# 05-WPT.net
KiCad netlist of a schematic drawn in Altium Designer
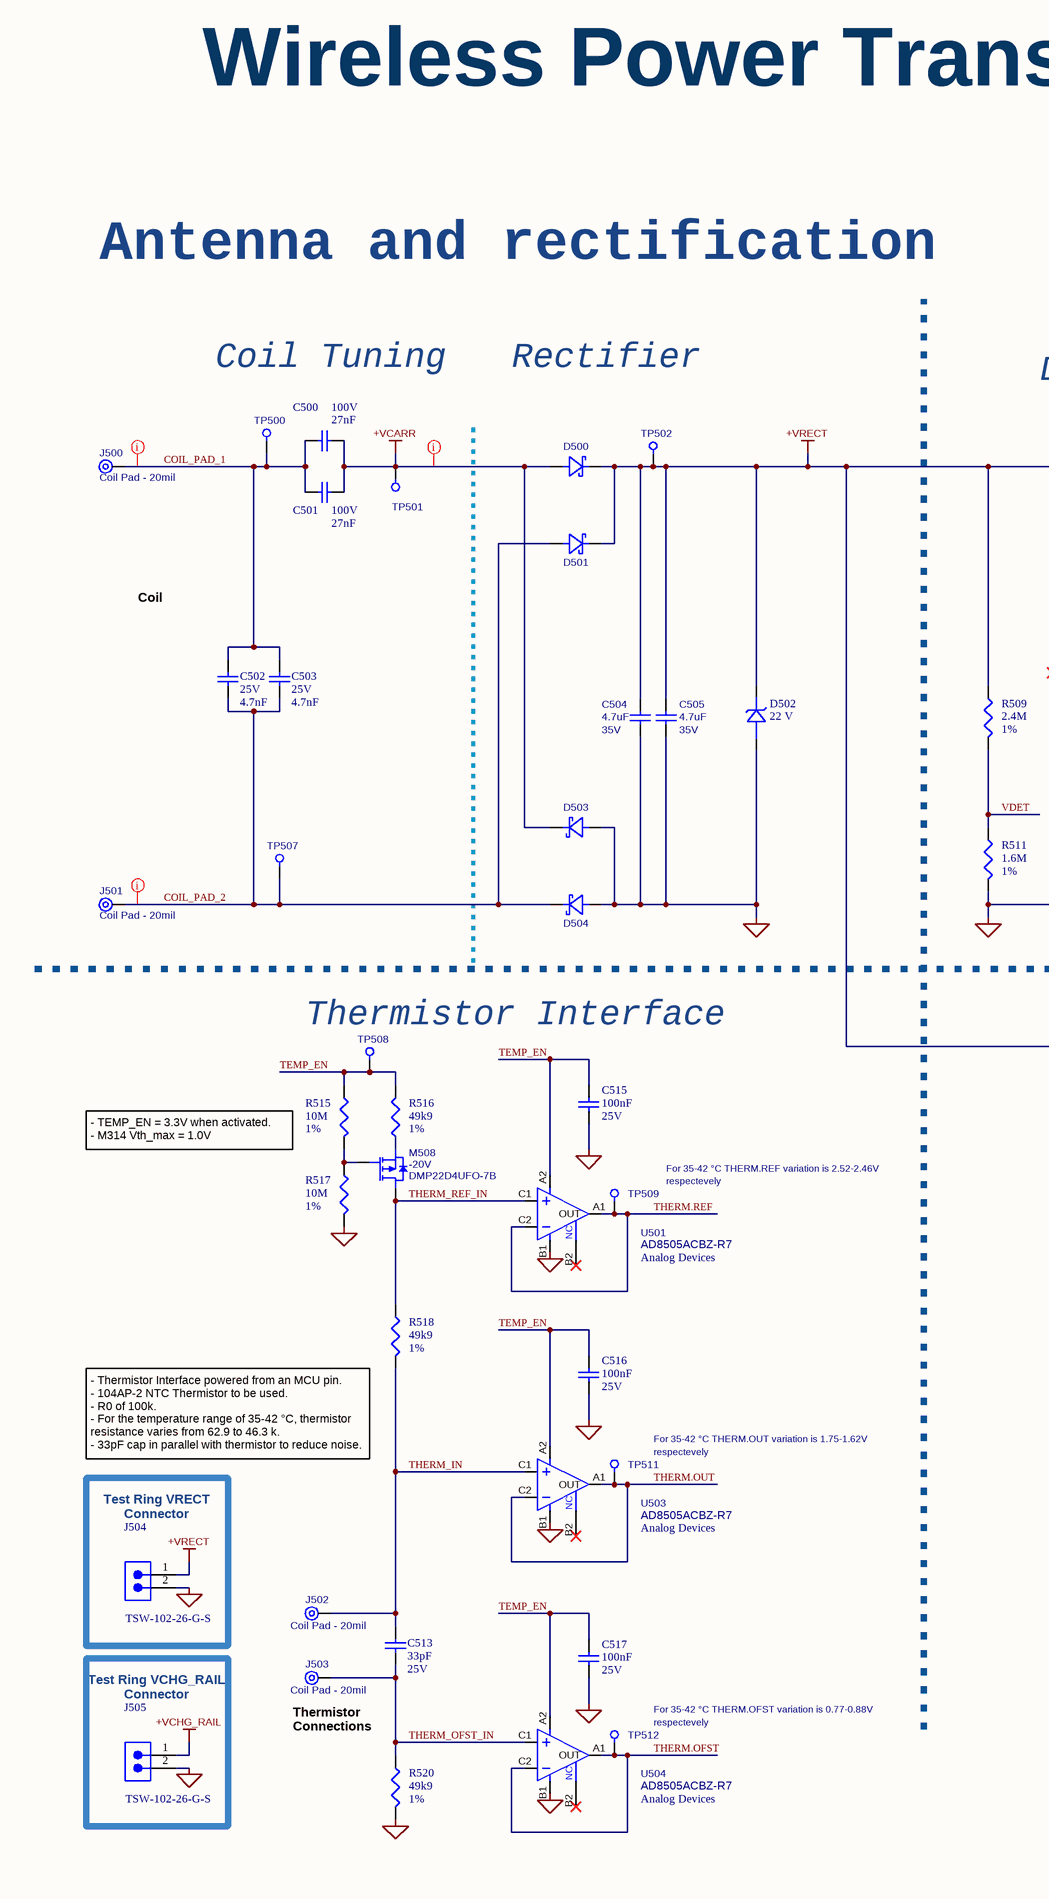
[diagram p0: 05-WPT.SchDoc, left]
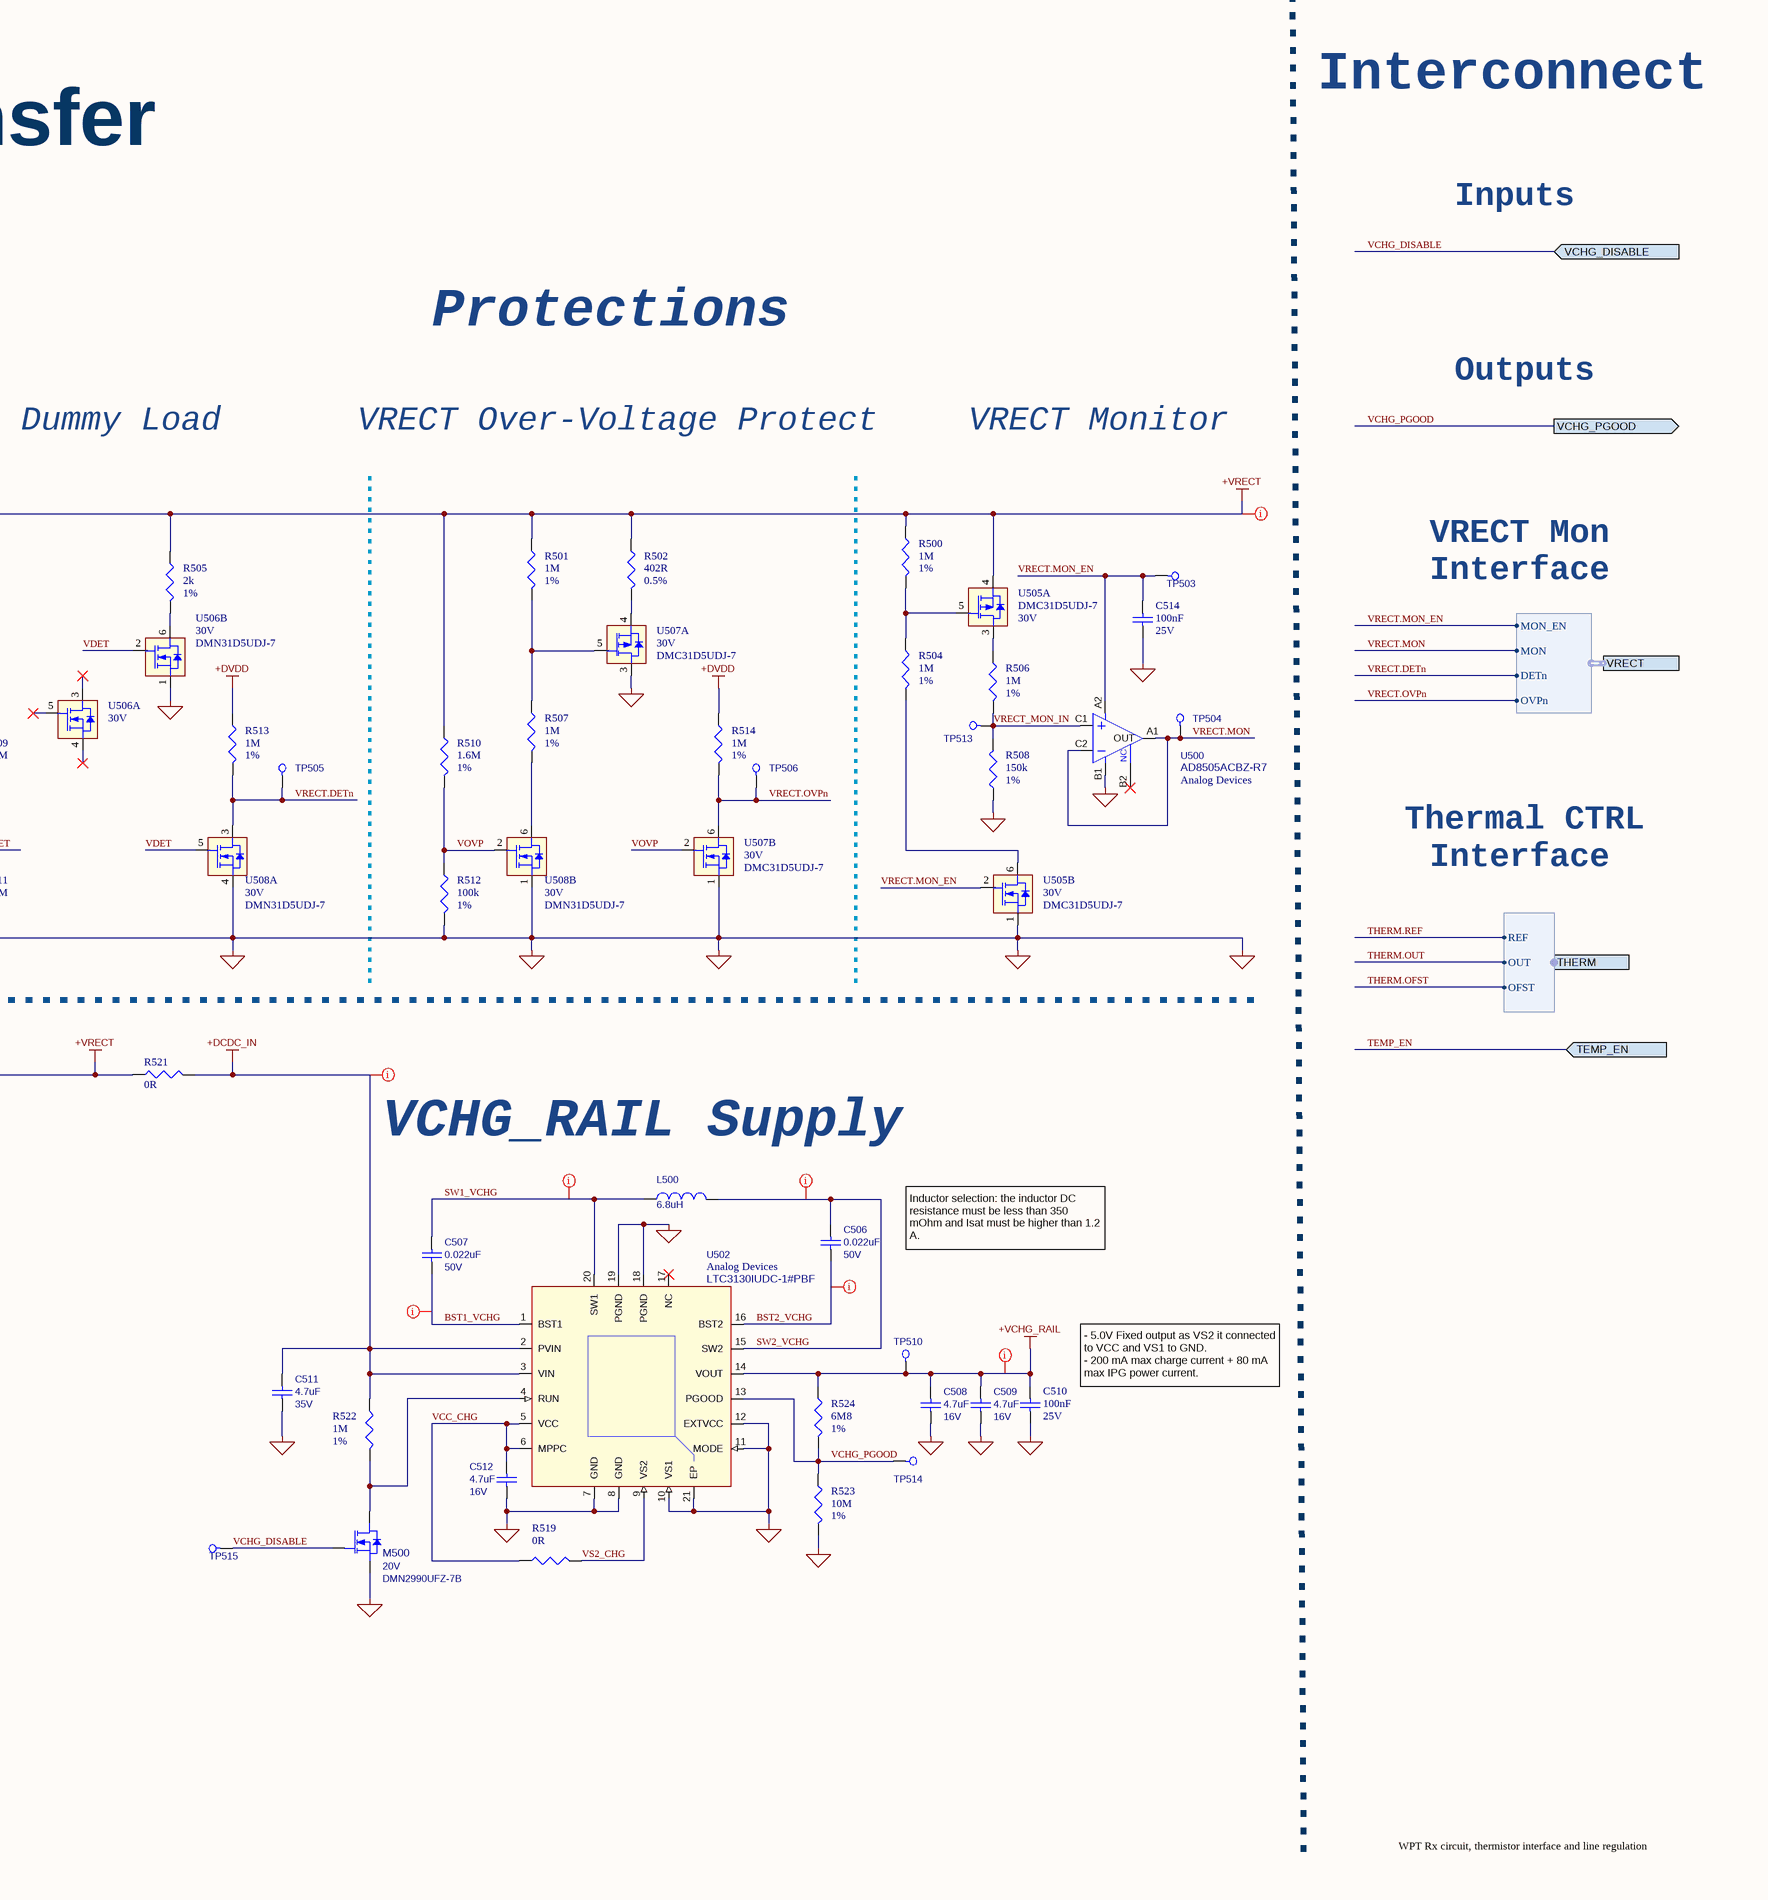
[diagram p1: 05-WPT.SchDoc, right]

(export (version "E")
  (design (tool "Eeschema 10.0.6"))
  (components
    (comp (ref "C500")
      (value "27nF")
      (footprint "CAP0805_REDUCED")
      (description "Capacitor, 27nF, C0G, 100VDC, 2%, 0805, Implant-grade")
      (fields
        (field (name "MANUFACTURER") "Murata")
        (field (name "MANUFACTURER PART NUMBER") "GRM2195C2A273GE01D")
        (field (name "VOLTAGE RATING") "100V")
      )
      (libsource (lib "MP-LIBRARY") (part "GRM2195C2A273GE01D"))
    )
    (comp (ref "C501")
      (value "27nF")
      (footprint "CAP0805_REDUCED")
      (description "Capacitor, 27nF, C0G, 100VDC, 2%, 0805, Implant-grade")
      (fields
        (field (name "MANUFACTURER") "Murata")
        (field (name "MANUFACTURER PART NUMBER") "GRM2195C2A273GE01D")
        (field (name "VOLTAGE RATING") "100V")
      )
      (libsource (lib "MP-LIBRARY") (part "GRM2195C2A273GE01D"))
    )
    (comp (ref "C502")
      (value "4.7nF")
      (footprint "CAP0603_REDUCED")
      (description "Capacitor, 4.7nF, C0G, 25V, 1%, 0603, Implant-grade")
      (fields
        (field (name "MANUFACTURER") "KEMET")
        (field (name "MANUFACTURER PART NUMBER") "C0603C472F3GECTU")
        (field (name "VOLTAGE RATING") "25V")
      )
      (libsource (lib "MP-LIBRARY") (part "C0603C472F3GECTU"))
    )
    (comp (ref "C503")
      (value "4.7nF")
      (footprint "CAP0603_REDUCED")
      (description "Capacitor, 4.7nF, C0G, 25V, 1%, 0603, Implant-grade")
      (fields
        (field (name "MANUFACTURER") "KEMET")
        (field (name "MANUFACTURER PART NUMBER") "C0603C472F3GECTU")
        (field (name "VOLTAGE RATING") "25V")
      )
      (libsource (lib "MP-LIBRARY") (part "C0603C472F3GECTU"))
    )
    (comp (ref "C504")
      (value "4.7uF")
      (footprint "CAP0805_REDUCED")
      (description "Capacitor, 4.7uF, X7S, 35V, 10%, 0805, Implant-grade")
      (fields
        (field (name "MANUFACTURER") "Murata")
        (field (name "RATING") "35V")
        (field (name "MANUFACTURER PART NUMBER") "GCM21BC7YA475KE36L")
      )
      (libsource (lib "MP-LIBRARY") (part "GCM21BC7YA475KE36L"))
    )
    (comp (ref "C505")
      (value "4.7uF")
      (footprint "CAP0805_REDUCED")
      (description "Capacitor, 4.7uF, X7S, 35V, 10%, 0805, Implant-grade")
      (fields
        (field (name "MANUFACTURER") "Murata")
        (field (name "RATING") "35V")
        (field (name "MANUFACTURER PART NUMBER") "GCM21BC7YA475KE36L")
      )
      (libsource (lib "MP-LIBRARY") (part "GCM21BC7YA475KE36L"))
    )
    (comp (ref "C506")
      (value "0.022uF")
      (footprint "CAP0402_REDUCED")
      (description "Capacitor, 0.022uF, X7R, 50V, 10%, 0402, Implant-grade")
      (fields
        (field (name "MANUFACTURER") "Murata")
        (field (name "RATING") "50V")
        (field (name "MANUFACTURER PART NUMBER") "GCM155R71H223KA55D")
      )
      (libsource (lib "MP-LIBRARY") (part "GCM155R71H223KA55D"))
    )
    (comp (ref "C507")
      (value "0.022uF")
      (footprint "CAP0402_REDUCED")
      (description "Capacitor, 0.022uF, X7R, 50V, 10%, 0402, Implant-grade")
      (fields
        (field (name "MANUFACTURER") "Murata")
        (field (name "RATING") "50V")
        (field (name "MANUFACTURER PART NUMBER") "GCM155R71H223KA55D")
      )
      (libsource (lib "MP-LIBRARY") (part "GCM155R71H223KA55D"))
    )
    (comp (ref "C508")
      (value "4.7uF")
      (footprint "CAP0603_REDUCED")
      (description "Capacitor, 4.7uF, X5R, 16V, 10%, 0603, Implant-grade")
      (fields
        (field (name "MANUFACTURER") "Murata")
        (field (name "RATING") "16V")
        (field (name "MANUFACTURER PART NUMBER") "GRM188R61C475KE11")
      )
      (libsource (lib "MP-LIBRARY") (part "GRM188R61C475KE11"))
    )
    (comp (ref "C509")
      (value "4.7uF")
      (footprint "CAP0603_REDUCED")
      (description "Capacitor, 4.7uF, X5R, 16V, 10%, 0603, Implant-grade")
      (fields
        (field (name "MANUFACTURER") "Murata")
        (field (name "RATING") "16V")
        (field (name "MANUFACTURER PART NUMBER") "GRM188R61C475KE11")
      )
      (libsource (lib "MP-LIBRARY") (part "GRM188R61C475KE11"))
    )
    (comp (ref "C510")
      (value "100nF")
      (footprint "C0201_C")
      (fields
        (field (name "MANUFACTURER") "Murata")
        (field (name "MANUFACTURER PART NUMBER") "GRM033R61E104KE14J")
        (field (name "RATED DC VOLTAGE (URDC)") "25V")
      )
      (libsource (lib "MP-LIBRARY") (part "GRM033R61E104KE14J"))
    )
    (comp (ref "C511")
      (value "4.7uF")
      (footprint "CAP0805_REDUCED")
      (description "Capacitor, 4.7uF, X7S, 35V, 10%, 0805, Implant-grade")
      (fields
        (field (name "MANUFACTURER") "Murata")
        (field (name "RATING") "35V")
        (field (name "MANUFACTURER PART NUMBER") "GCM21BC7YA475KE36L")
      )
      (libsource (lib "MP-LIBRARY") (part "GCM21BC7YA475KE36L"))
    )
    (comp (ref "C512")
      (value "4.7uF")
      (footprint "CAP0603_REDUCED")
      (description "Capacitor, 4.7uF, X5R, 16V, 10%, 0603, Implant-grade")
      (fields
        (field (name "MANUFACTURER") "Murata")
        (field (name "RATING") "16V")
        (field (name "MANUFACTURER PART NUMBER") "GRM188R61C475KE11")
      )
      (libsource (lib "MP-LIBRARY") (part "GRM188R61C475KE11"))
    )
    (comp (ref "C513")
      (value "33pF")
      (footprint "C0201_C")
      (fields
        (field (name "MANUFACTURER") "Murata")
        (field (name "MANUFACTURER PART NUMBER") "GRM0335C1E330JA01D")
        (field (name "RATED DC VOLTAGE (URDC)") "25V")
      )
      (libsource (lib "MP-LIBRARY") (part "GRM0335C1E330JA01D"))
    )
    (comp (ref "C514")
      (value "100nF")
      (footprint "C0201_C")
      (fields
        (field (name "MANUFACTURER") "Murata")
        (field (name "MANUFACTURER PART NUMBER") "GRM033R61E104KE14J")
        (field (name "RATED DC VOLTAGE (URDC)") "25V")
      )
      (libsource (lib "MP-LIBRARY") (part "GRM033R61E104KE14J"))
    )
    (comp (ref "C515")
      (value "100nF")
      (footprint "C0201_C")
      (fields
        (field (name "MANUFACTURER") "Murata")
        (field (name "MANUFACTURER PART NUMBER") "GRM033R61E104KE14J")
        (field (name "RATED DC VOLTAGE (URDC)") "25V")
      )
      (libsource (lib "MP-LIBRARY") (part "GRM033R61E104KE14J"))
    )
    (comp (ref "C516")
      (value "100nF")
      (footprint "C0201_C")
      (fields
        (field (name "MANUFACTURER") "Murata")
        (field (name "MANUFACTURER PART NUMBER") "GRM033R61E104KE14J")
        (field (name "RATED DC VOLTAGE (URDC)") "25V")
      )
      (libsource (lib "MP-LIBRARY") (part "GRM033R61E104KE14J"))
    )
    (comp (ref "C517")
      (value "100nF")
      (footprint "C0201_C")
      (fields
        (field (name "MANUFACTURER") "Murata")
        (field (name "MANUFACTURER PART NUMBER") "GRM033R61E104KE14J")
        (field (name "RATED DC VOLTAGE (URDC)") "25V")
      )
      (libsource (lib "MP-LIBRARY") (part "GRM033R61E104KE14J"))
    )
    (comp (ref "D500")
      (value "GSBT0540X")
      (footprint "STM_SOD-523_R")
      (description "DIODE SCHOTTKY 40V 500MA SOD523")
      (fields (field (name "MANUFACTURER") "Good-Ark Semiconductor"))
      (libsource (lib "MP-LIBRARY") (part "GSBT0540X"))
    )
    (comp (ref "D501")
      (value "GSBT0540X")
      (footprint "STM_SOD-523_R")
      (description "DIODE SCHOTTKY 40V 500MA SOD523")
      (fields (field (name "MANUFACTURER") "Good-Ark Semiconductor"))
      (libsource (lib "MP-LIBRARY") (part "GSBT0540X"))
    )
    (comp (ref "D502")
      (value "MM5Z22VT5G")
      (footprint "SODFL1608X70N")
      (description "ZEN SOD523 LOW IZ REG 0.5W 22V")
      (fields (field (name "MANUFACTURER") "onsemi") (field (name "BREAKDOWN VOLTAGE") "22 V"))
      (libsource (lib "MP-LIBRARY") (part "MM5Z22VT5G"))
    )
    (comp (ref "D503")
      (value "GSBT0540X")
      (footprint "STM_SOD-523_R")
      (description "DIODE SCHOTTKY 40V 500MA SOD523")
      (fields (field (name "MANUFACTURER") "Good-Ark Semiconductor"))
      (libsource (lib "MP-LIBRARY") (part "GSBT0540X"))
    )
    (comp (ref "D504")
      (value "GSBT0540X")
      (footprint "STM_SOD-523_R")
      (description "DIODE SCHOTTKY 40V 500MA SOD523")
      (fields (field (name "MANUFACTURER") "Good-Ark Semiconductor"))
      (libsource (lib "MP-LIBRARY") (part "GSBT0540X"))
    )
    (comp (ref "J500")
      (value "Coil Pad - 20mil")
      (footprint "FEEDHOLE_20mil")
      (description "Coil TH pad, 20mil")
      (libsource (lib "MP-LIBRARY") (part "Coil Pad - 20mil"))
    )
    (comp (ref "J501")
      (value "Coil Pad - 20mil")
      (footprint "FEEDHOLE_20mil")
      (description "Coil TH pad, 20mil")
      (libsource (lib "MP-LIBRARY") (part "Coil Pad - 20mil"))
    )
    (comp (ref "J502")
      (value "Coil Pad - 20mil")
      (footprint "FEEDHOLE_20mil")
      (description "Coil TH pad, 20mil")
      (libsource (lib "MP-LIBRARY") (part "Coil Pad - 20mil"))
    )
    (comp (ref "J503")
      (value "Coil Pad - 20mil")
      (footprint "FEEDHOLE_20mil")
      (description "Coil TH pad, 20mil")
      (libsource (lib "MP-LIBRARY") (part "Coil Pad - 20mil"))
    )
    (comp (ref "J504")
      (value "TSW-102-26-G-S")
      (footprint "SMTC-TSW-102-26-XX-S")
      (description "Conn Unshrouded Header HDR 2 POS 2.54mm Solder ST Thru-Hole")
      (fields (field (name "MANUFACTURER") "Samtec"))
      (libsource (lib "MP-LIBRARY") (part "TSW-102-26-G-S"))
    )
    (comp (ref "J505")
      (value "TSW-102-26-G-S")
      (footprint "SMTC-TSW-102-26-XX-S")
      (description "Conn Unshrouded Header HDR 2 POS 2.54mm Solder ST Thru-Hole")
      (fields (field (name "MANUFACTURER") "Samtec"))
      (libsource (lib "MP-LIBRARY") (part "TSW-102-26-G-S"))
    )
    (comp (ref "L500")
      (value "6.8uH")
      (footprint "LSEUC2520KKT6R8M")
      (description "6.8 µH Unshielded Wirewound Inductor 1.3 A 265mOhm Max 1008 (2520 Metric)")
      (fields
        (field (name "MANUFACTURER") "Taiyo Yuden")
        (field (name "MANUFACTURER PART NUMBER") "LSEUC2520KKT6R8M")
      )
      (libsource (lib "MP-LIBRARY") (part "LSEUC2520KKT6R8M"))
    )
    (comp (ref "M500")
      (value "DMN2990UFZ-7B")
      (footprint "DIODESINC_X2-DFN0606-3")
      (description "MOSFET, N-Chan, 20V, 170mA, DFN0606")
      (fields (field (name "MANUFACTURER") "Diodes Inc") (field (name "RATING") "20V"))
      (libsource (lib "MP-LIBRARY") (part "DMN2990UFZ-7B"))
    )
    (comp (ref "M508")
      (value "DMP22D4UFO-7B")
      (footprint "DIODESINC_X2-DFN0604-3")
      (description "MOSFET, P-chan, -20V, -383mA, DFN0604")
      (fields (field (name "MANUFACTURER") "Diodes Inc") (field (name "RATING") "-20V"))
      (libsource (lib "MP-LIBRARY") (part "DMP22D4UFO-7B"))
    )
    (comp (ref "R500")
      (value "1M")
      (footprint "R0201_C")
      (fields
        (field (name "MANUFACTURER") "Vishay")
        (field (name "MANUFACTURER PART NUMBER") "CRCW02011M00FNED")
        (field (name "TOLERANCE") "1%")
        (field (name "POWER") "50mW")
      )
      (libsource (lib "MP-LIBRARY") (part "CRCW02011M00FNED"))
    )
    (comp (ref "R501")
      (value "1M")
      (footprint "R0201_C")
      (fields
        (field (name "MANUFACTURER") "Vishay")
        (field (name "MANUFACTURER PART NUMBER") "CRCW02011M00FNED")
        (field (name "TOLERANCE") "1%")
        (field (name "POWER") "50mW")
      )
      (libsource (lib "MP-LIBRARY") (part "CRCW02011M00FNED"))
    )
    (comp (ref "R502")
      (value "402R")
      (footprint "R0603")
      (fields
        (field (name "MANUFACTURER") "Vishay")
        (field (name "MANUFACTURER PART NUMBER") "SDR03EZPD4020")
        (field (name "TOLERANCE") "0.5%")
        (field (name "POWER") "400mW")
      )
      (libsource (lib "MP-LIBRARY") (part "SDR03EZPD4020"))
    )
    (comp (ref "R504")
      (value "1M")
      (footprint "R0201_C")
      (fields
        (field (name "MANUFACTURER") "Vishay")
        (field (name "MANUFACTURER PART NUMBER") "CRCW02011M00FNED")
        (field (name "TOLERANCE") "1%")
        (field (name "POWER") "50mW")
      )
      (libsource (lib "MP-LIBRARY") (part "CRCW02011M00FNED"))
    )
    (comp (ref "R505")
      (value "2k")
      (footprint "R0201_C")
      (fields
        (field (name "MANUFACTURER") "Vishay Dale")
        (field (name "MANUFACTURER PART NUMBER") "CRCW02012K00FNED")
        (field (name "TOLERANCE") "1%")
        (field (name "POWER") "50mW")
      )
      (libsource (lib "MP-LIBRARY") (part "CRCW02012K00FNED"))
    )
    (comp (ref "R506")
      (value "1M")
      (footprint "R0201_C")
      (fields
        (field (name "MANUFACTURER") "Vishay")
        (field (name "MANUFACTURER PART NUMBER") "CRCW02011M00FNED")
        (field (name "TOLERANCE") "1%")
        (field (name "POWER") "50mW")
      )
      (libsource (lib "MP-LIBRARY") (part "CRCW02011M00FNED"))
    )
    (comp (ref "R507")
      (value "1M")
      (footprint "R0201_C")
      (fields
        (field (name "MANUFACTURER") "Vishay")
        (field (name "MANUFACTURER PART NUMBER") "CRCW02011M00FNED")
        (field (name "TOLERANCE") "1%")
        (field (name "POWER") "50mW")
      )
      (libsource (lib "MP-LIBRARY") (part "CRCW02011M00FNED"))
    )
    (comp (ref "R508")
      (value "150k")
      (footprint "R0201_C")
      (description "150 kOhms ±1% 0.05W, 1/20W Chip Resistor 0201 (0603 Metric) Thick Film")
      (fields
        (field (name "MANUFACTURER") "Vishay Dale")
        (field (name "MANUFACTURER PART NUMBER") "CRCW0201150KFKED")
        (field (name "TOLERANCE") "1%")
      )
      (libsource (lib "MP-LIBRARY") (part "CRCW0201150KFKED"))
    )
    (comp (ref "R509")
      (value "2.4M")
      (footprint "R0201_C")
      (fields
        (field (name "MANUFACTURER") "Vishay Draloric")
        (field (name "MANUFACTURER PART NUMBER") "CRCW02012M40FNED")
        (field (name "TOLERANCE") "1%")
        (field (name "POWER") "50mW")
      )
      (libsource (lib "MP-LIBRARY") (part "CRCW02012M40FNED"))
    )
    (comp (ref "R510")
      (value "1.6M")
      (footprint "R0201_C")
      (fields
        (field (name "MANUFACTURER") "Vishay Dale")
        (field (name "MANUFACTURER PART NUMBER") "CRCW02011M60FNED")
        (field (name "TOLERANCE") "1%")
        (field (name "POWER") "50mW")
      )
      (libsource (lib "MP-LIBRARY") (part "CRCW02011M60FNED"))
    )
    (comp (ref "R511")
      (value "1.6M")
      (footprint "R0201_C")
      (fields
        (field (name "MANUFACTURER") "Vishay Dale")
        (field (name "MANUFACTURER PART NUMBER") "CRCW02011M60FNED")
        (field (name "TOLERANCE") "1%")
        (field (name "POWER") "50mW")
      )
      (libsource (lib "MP-LIBRARY") (part "CRCW02011M60FNED"))
    )
    (comp (ref "R512")
      (value "100k")
      (footprint "R0201_C")
      (fields
        (field (name "MANUFACTURER") "Vishay")
        (field (name "MANUFACTURER PART NUMBER") "CRCW0201100KFNED")
        (field (name "TOLERANCE") "1%")
        (field (name "POWER") "50mW")
      )
      (libsource (lib "MP-LIBRARY") (part "CRCW0201100KFNED"))
    )
    (comp (ref "R513")
      (value "1M")
      (footprint "R0201_C")
      (fields
        (field (name "MANUFACTURER") "Vishay")
        (field (name "MANUFACTURER PART NUMBER") "CRCW02011M00FNED")
        (field (name "TOLERANCE") "1%")
        (field (name "POWER") "50mW")
      )
      (libsource (lib "MP-LIBRARY") (part "CRCW02011M00FNED"))
    )
    (comp (ref "R514")
      (value "1M")
      (footprint "R0201_C")
      (fields
        (field (name "MANUFACTURER") "Vishay")
        (field (name "MANUFACTURER PART NUMBER") "CRCW02011M00FNED")
        (field (name "TOLERANCE") "1%")
        (field (name "POWER") "50mW")
      )
      (libsource (lib "MP-LIBRARY") (part "CRCW02011M00FNED"))
    )
    (comp (ref "R515")
      (value "10M")
      (footprint "R0201_C")
      (fields
        (field (name "MANUFACTURER") "Vishay Draloric")
        (field (name "MANUFACTURER PART NUMBER") "CRCW020110M0FNED")
        (field (name "TOLERANCE") "1%")
        (field (name "POWER") "50mW")
      )
      (libsource (lib "MP-LIBRARY") (part "CRCW020110M0FNED"))
    )
    (comp (ref "R516")
      (value "49k9")
      (footprint "R0201_C")
      (fields
        (field (name "MANUFACTURER") "Vishay")
        (field (name "MANUFACTURER PART NUMBER") "CRCW020149K9FNED")
        (field (name "TOLERANCE") "1%")
        (field (name "POWER") "50mW")
      )
      (libsource (lib "MP-LIBRARY") (part "CRCW020149K9FNED"))
    )
    (comp (ref "R517")
      (value "10M")
      (footprint "R0201_C")
      (fields
        (field (name "MANUFACTURER") "Vishay Draloric")
        (field (name "MANUFACTURER PART NUMBER") "CRCW020110M0FNED")
        (field (name "TOLERANCE") "1%")
        (field (name "POWER") "50mW")
      )
      (libsource (lib "MP-LIBRARY") (part "CRCW020110M0FNED"))
    )
    (comp (ref "R518")
      (value "49k9")
      (footprint "R0201_C")
      (fields
        (field (name "MANUFACTURER") "Vishay")
        (field (name "MANUFACTURER PART NUMBER") "CRCW020149K9FNED")
        (field (name "TOLERANCE") "1%")
        (field (name "POWER") "50mW")
      )
      (libsource (lib "MP-LIBRARY") (part "CRCW020149K9FNED"))
    )
    (comp (ref "R519")
      (value "0R")
      (footprint "R0201_C")
      (description "Fixed Resistor, Metal Glaze/thick Film, 0.05W, 0ohm, Surface Mount, 0201")
      (fields
        (field (name "MANUFACTURER") "Vishay")
        (field (name "MANUFACTURER PART NUMBER") "CRCW02010000Z0ED")
      )
      (libsource (lib "MP-LIBRARY") (part "CRCW02010000Z0ED"))
    )
    (comp (ref "R520")
      (value "49k9")
      (footprint "R0201_C")
      (fields
        (field (name "MANUFACTURER") "Vishay")
        (field (name "MANUFACTURER PART NUMBER") "CRCW020149K9FNED")
        (field (name "TOLERANCE") "1%")
        (field (name "POWER") "50mW")
      )
      (libsource (lib "MP-LIBRARY") (part "CRCW020149K9FNED"))
    )
    (comp (ref "R521")
      (value "0R")
      (footprint "R0201_C")
      (description "Fixed Resistor, Metal Glaze/thick Film, 0.05W, 0ohm, Surface Mount, 0201")
      (fields
        (field (name "MANUFACTURER") "Vishay")
        (field (name "MANUFACTURER PART NUMBER") "CRCW02010000Z0ED")
      )
      (libsource (lib "MP-LIBRARY") (part "CRCW02010000Z0ED"))
    )
    (comp (ref "R522")
      (value "1M")
      (footprint "R0201_C")
      (fields
        (field (name "MANUFACTURER") "Vishay")
        (field (name "MANUFACTURER PART NUMBER") "CRCW02011M00FNED")
        (field (name "TOLERANCE") "1%")
        (field (name "POWER") "50mW")
      )
      (libsource (lib "MP-LIBRARY") (part "CRCW02011M00FNED"))
    )
    (comp (ref "R523")
      (value "10M")
      (footprint "R0201_C")
      (fields
        (field (name "MANUFACTURER") "Vishay Draloric")
        (field (name "MANUFACTURER PART NUMBER") "CRCW020110M0FNED")
        (field (name "TOLERANCE") "1%")
        (field (name "POWER") "50mW")
      )
      (libsource (lib "MP-LIBRARY") (part "CRCW020110M0FNED"))
    )
    (comp (ref "R524")
      (value "6M8")
      (footprint "R0201_C")
      (fields
        (field (name "MANUFACTURER") "Vishay Draloric")
        (field (name "MANUFACTURER PART NUMBER") "CRCW02016M80FNED")
        (field (name "TOLERANCE") "1%")
        (field (name "POWER") "50mW")
      )
      (libsource (lib "MP-LIBRARY") (part "CRCW02016M80FNED"))
    )
    (comp (ref "TP500")
      (value "Test Point")
      (footprint "testpad_0.9mm")
      (description "Test pad, 0.90mm circular pad")
      (libsource (lib "MP-LIBRARY") (part "Test Point"))
    )
    (comp (ref "TP501")
      (value "Test Point")
      (footprint "testpad_0.9mm")
      (description "Test pad, 0.90mm circular pad")
      (libsource (lib "MP-LIBRARY") (part "Test Point"))
    )
    (comp (ref "TP502")
      (value "Test Point")
      (footprint "testpad_0.9mm")
      (description "Test pad, 0.90mm circular pad")
      (libsource (lib "MP-LIBRARY") (part "Test Point"))
    )
    (comp (ref "TP503")
      (value "Test Point")
      (footprint "testpad_0.9mm")
      (description "Test pad, 0.90mm circular pad")
      (libsource (lib "MP-LIBRARY") (part "Test Point"))
    )
    (comp (ref "TP504")
      (value "Test Point")
      (footprint "testpad_0.9mm")
      (description "Test pad, 0.90mm circular pad")
      (libsource (lib "MP-LIBRARY") (part "Test Point"))
    )
    (comp (ref "TP505")
      (value "Test Point")
      (footprint "testpad_0.9mm")
      (description "Test pad, 0.90mm circular pad")
      (libsource (lib "MP-LIBRARY") (part "Test Point"))
    )
    (comp (ref "TP506")
      (value "Test Point")
      (footprint "testpad_0.9mm")
      (description "Test pad, 0.90mm circular pad")
      (libsource (lib "MP-LIBRARY") (part "Test Point"))
    )
    (comp (ref "TP507")
      (value "Test Point")
      (footprint "testpad_0.9mm")
      (description "Test pad, 0.90mm circular pad")
      (libsource (lib "MP-LIBRARY") (part "Test Point"))
    )
    (comp (ref "TP508")
      (value "Test Point")
      (footprint "testpad_0.9mm")
      (description "Test pad, 0.90mm circular pad")
      (libsource (lib "MP-LIBRARY") (part "Test Point"))
    )
    (comp (ref "TP509")
      (value "Test Point")
      (footprint "testpad_0.9mm")
      (description "Test pad, 0.90mm circular pad")
      (libsource (lib "MP-LIBRARY") (part "Test Point"))
    )
    (comp (ref "TP510")
      (value "Test Point")
      (footprint "testpad_0.9mm")
      (description "Test pad, 0.90mm circular pad")
      (libsource (lib "MP-LIBRARY") (part "Test Point"))
    )
    (comp (ref "TP511")
      (value "Test Point")
      (footprint "testpad_0.9mm")
      (description "Test pad, 0.90mm circular pad")
      (libsource (lib "MP-LIBRARY") (part "Test Point"))
    )
    (comp (ref "TP512")
      (value "Test Point")
      (footprint "testpad_0.9mm")
      (description "Test pad, 0.90mm circular pad")
      (libsource (lib "MP-LIBRARY") (part "Test Point"))
    )
    (comp (ref "TP513")
      (value "Test Point")
      (footprint "testpad_0.9mm")
      (description "Test pad, 0.90mm circular pad")
      (libsource (lib "MP-LIBRARY") (part "Test Point"))
    )
    (comp (ref "TP514")
      (value "Test Point")
      (footprint "testpad_0.9mm")
      (description "Test pad, 0.90mm circular pad")
      (libsource (lib "MP-LIBRARY") (part "Test Point"))
    )
    (comp (ref "TP515")
      (value "Test Point")
      (footprint "testpad_0.9mm")
      (description "Test pad, 0.90mm circular pad")
      (libsource (lib "MP-LIBRARY") (part "Test Point"))
    )
    (comp (ref "U500")
      (value "AD8505ACBZ-R7")
      (footprint "AD8505ACBZ-R7")
      (description "Op Amp, Rail-to-Rail, 95kHz, WLCSP-6")
      (fields (field (name "MANUFACTURER") "Analog Devices"))
      (libsource (lib "MP-LIBRARY") (part "AD8505ACBZ-R7"))
    )
    (comp (ref "U501")
      (value "AD8505ACBZ-R7")
      (footprint "AD8505ACBZ-R7")
      (description "Op Amp, Rail-to-Rail, 95kHz, WLCSP-6")
      (fields (field (name "MANUFACTURER") "Analog Devices"))
      (libsource (lib "MP-LIBRARY") (part "AD8505ACBZ-R7"))
    )
    (comp (ref "U502")
      (value "LTC3130IUDC-1#PBF")
      (footprint "LT_UDC-20_REDUCED")
      (description "Buck-Boost Converter, Selectable Voltage, QFN-20")
      (fields (field (name "MANUFACTURER") "Analog Devices"))
      (libsource (lib "MP-LIBRARY") (part "LTC3130IUDC-1#PBF"))
    )
    (comp (ref "U503")
      (value "AD8505ACBZ-R7")
      (footprint "AD8505ACBZ-R7")
      (description "Op Amp, Rail-to-Rail, 95kHz, WLCSP-6")
      (fields (field (name "MANUFACTURER") "Analog Devices"))
      (libsource (lib "MP-LIBRARY") (part "AD8505ACBZ-R7"))
    )
    (comp (ref "U504")
      (value "AD8505ACBZ-R7")
      (footprint "AD8505ACBZ-R7")
      (description "Op Amp, Rail-to-Rail, 95kHz, WLCSP-6")
      (fields (field (name "MANUFACTURER") "Analog Devices"))
      (libsource (lib "MP-LIBRARY") (part "AD8505ACBZ-R7"))
    )
    (comp (ref "U505")
      (value "DMC31D5UDJ-7")
      (footprint "DIODESINC_SOT-963-6")
      (description "MOSFET N/P-CH 30V 0.22A SOT963")
      (fields (field (name "MANUFACTURER") "Diodes inc.") (field (name "VDS(MAX)") "30V"))
      (libsource (lib "") (part "DMC31D5UDJ-7_1"))
    )
    (comp (ref "U506")
      (value "DMN31D5UDJ-7")
      (footprint "DIODESINC_SOT-963-6")
      (description "MOSFET 2N-CH 30V 0.22A SOT963")
      (fields (field (name "MANUFACTURER") "Diodes inc.") (field (name "VDS(MAX)") "30V"))
      (libsource (lib "MP-LIBRARY") (part "DMN31D5UDJ-7"))
    )
    (comp (ref "U507")
      (value "DMC31D5UDJ-7")
      (footprint "DIODESINC_SOT-963-6")
      (description "MOSFET N/P-CH 30V 0.22A SOT963")
      (fields (field (name "MANUFACTURER") "Diodes inc.") (field (name "VDS(MAX)") "30V"))
      (libsource (lib "MP-LIBRARY") (part "DMC31D5UDJ-7"))
    )
    (comp (ref "U508")
      (value "DMN31D5UDJ-7")
      (footprint "DIODESINC_SOT-963-6")
      (description "MOSFET 2N-CH 30V 0.22A SOT963")
      (fields (field (name "MANUFACTURER") "Diodes inc.") (field (name "VDS(MAX)") "30V"))
      (libsource (lib "MP-LIBRARY") (part "DMN31D5UDJ-7"))
    )
  )
  (nets
    (net (code "4") (name "+DCDC_IN") (class "Default")
      (node (ref "C511") (pin "2") (pinfunction "2_2") (pintype "passive"))
      (node (ref "R521") (pin "2") (pinfunction "2_2") (pintype "passive"))
      (node (ref "R522") (pin "1") (pinfunction "1_1") (pintype "passive"))
      (node (ref "U502") (pin "2") (pinfunction "PVIN_2") (pintype "power_in"))
      (node (ref "U502") (pin "3") (pinfunction "VIN_3") (pintype "power_in"))
    )
    (net (code "5") (name "+DVDD") (class "Default")
      (node (ref "R513") (pin "1") (pinfunction "1_1") (pintype "passive"))
      (node (ref "R514") (pin "1") (pinfunction "1_1") (pintype "passive"))
    )
    (net (code "6") (name "+VCARR") (class "Default")
      (node (ref "C500") (pin "2") (pinfunction "2_2") (pintype "passive"))
      (node (ref "C501") (pin "2") (pinfunction "2_2") (pintype "passive"))
      (node (ref "D500") (pin "2") (pinfunction "2_2") (pintype "passive"))
      (node (ref "D503") (pin "1") (pinfunction "1_1") (pintype "passive"))
      (node (ref "TP501") (pin "1") (pinfunction "1_1") (pintype "passive"))
    )
    (net (code "7") (name "+VCHG_RAIL") (class "Default")
      (node (ref "C508") (pin "1") (pinfunction "1_1") (pintype "passive"))
      (node (ref "C509") (pin "1") (pinfunction "1_1") (pintype "passive"))
      (node (ref "C510") (pin "2") (pinfunction "2_2") (pintype "passive"))
      (node (ref "J505") (pin "1") (pinfunction "1_1") (pintype "passive"))
      (node (ref "R524") (pin "1") (pinfunction "1_1") (pintype "passive"))
      (node (ref "TP510") (pin "1") (pinfunction "1_1") (pintype "passive"))
      (node (ref "U502") (pin "14") (pinfunction "VOUT_14") (pintype "power_in"))
    )
    (net (code "8") (name "+VRECT") (class "Default")
      (node (ref "C504") (pin "2") (pinfunction "2_2") (pintype "passive"))
      (node (ref "C505") (pin "2") (pinfunction "2_2") (pintype "passive"))
      (node (ref "D500") (pin "1") (pinfunction "1_1") (pintype "passive"))
      (node (ref "D501") (pin "1") (pinfunction "1_1") (pintype "passive"))
      (node (ref "D502") (pin "1") (pinfunction "K1_1") (pintype "passive"))
      (node (ref "J504") (pin "1") (pinfunction "1_1") (pintype "passive"))
      (node (ref "R500") (pin "1") (pinfunction "1_1") (pintype "passive"))
      (node (ref "R501") (pin "1") (pinfunction "1_1") (pintype "passive"))
      (node (ref "R502") (pin "1") (pinfunction "1_1") (pintype "passive"))
      (node (ref "R505") (pin "1") (pinfunction "1_1") (pintype "passive"))
      (node (ref "R509") (pin "1") (pinfunction "1_1") (pintype "passive"))
      (node (ref "R510") (pin "1") (pinfunction "1_1") (pintype "passive"))
      (node (ref "R521") (pin "1") (pinfunction "1_1") (pintype "passive"))
      (node (ref "TP502") (pin "1") (pinfunction "1_1") (pintype "passive"))
      (node (ref "U505") (pin "4") (pinfunction "4_4") (pintype "passive"))
    )
    (net (code "9") (name "/BST1_VCHG") (class "Default")
      (node (ref "C507") (pin "1") (pinfunction "1_1") (pintype "passive"))
      (node (ref "U502") (pin "1") (pinfunction "BST1_1") (pintype "passive"))
    )
    (net (code "10") (name "/BST2_VCHG") (class "Default")
      (node (ref "C506") (pin "1") (pinfunction "1_1") (pintype "passive"))
      (node (ref "U502") (pin "16") (pinfunction "BST2_16") (pintype "passive"))
    )
    (net (code "11") (name "/COIL_PAD_1") (class "Default")
      (node (ref "C500") (pin "1") (pinfunction "1_1") (pintype "passive"))
      (node (ref "C501") (pin "1") (pinfunction "1_1") (pintype "passive"))
      (node (ref "C502") (pin "2") (pinfunction "2_2") (pintype "passive"))
      (node (ref "C503") (pin "2") (pinfunction "2_2") (pintype "passive"))
      (node (ref "J500") (pin "1") (pinfunction "1_1") (pintype "passive"))
      (node (ref "TP500") (pin "1") (pinfunction "1_1") (pintype "passive"))
    )
    (net (code "12") (name "/COIL_PAD_2") (class "Default")
      (node (ref "C502") (pin "1") (pinfunction "1_1") (pintype "passive"))
      (node (ref "C503") (pin "1") (pinfunction "1_1") (pintype "passive"))
      (node (ref "D501") (pin "2") (pinfunction "2_2") (pintype "passive"))
      (node (ref "D504") (pin "1") (pinfunction "1_1") (pintype "passive"))
      (node (ref "J501") (pin "1") (pinfunction "1_1") (pintype "passive"))
      (node (ref "TP507") (pin "1") (pinfunction "1_1") (pintype "passive"))
    )
    (net (code "13") (name "/SW1_VCHG") (class "Default")
      (node (ref "C507") (pin "2") (pinfunction "2_2") (pintype "passive"))
      (node (ref "L500") (pin "1") (pinfunction "1_1") (pintype "passive"))
      (node (ref "U502") (pin "20") (pinfunction "SW1_20") (pintype "passive"))
    )
    (net (code "14") (name "/SW2_VCHG") (class "Default")
      (node (ref "C506") (pin "2") (pinfunction "2_2") (pintype "passive"))
      (node (ref "L500") (pin "2") (pinfunction "2_2") (pintype "passive"))
      (node (ref "U502") (pin "15") (pinfunction "SW2_15") (pintype "passive"))
    )
    (net (code "15") (name "/TEMP_EN") (class "Default")
      (node (ref "C515") (pin "2") (pinfunction "2_2") (pintype "passive"))
      (node (ref "C516") (pin "2") (pinfunction "2_2") (pintype "passive"))
      (node (ref "C517") (pin "2") (pinfunction "2_2") (pintype "passive"))
      (node (ref "R515") (pin "1") (pinfunction "1_1") (pintype "passive"))
      (node (ref "R516") (pin "2") (pinfunction "2_2") (pintype "passive"))
      (node (ref "TP508") (pin "1") (pinfunction "1_1") (pintype "passive"))
      (node (ref "U501") (pin "A2") (pinfunction "V+_A2") (pintype "power_in"))
      (node (ref "U503") (pin "A2") (pinfunction "V+_A2") (pintype "power_in"))
      (node (ref "U504") (pin "A2") (pinfunction "V+_A2") (pintype "power_in"))
    )
    (net (code "16") (name "/THERM.OFST") (class "Default")
      (node (ref "TP512") (pin "1") (pinfunction "1_1") (pintype "passive"))
      (node (ref "U504") (pin "A1") (pinfunction "OUT_A1") (pintype "passive"))
      (node (ref "U504") (pin "C2") (pinfunction "IN-_C2") (pintype "passive"))
    )
    (net (code "17") (name "/THERM.OUT") (class "Default")
      (node (ref "TP511") (pin "1") (pinfunction "1_1") (pintype "passive"))
      (node (ref "U503") (pin "A1") (pinfunction "OUT_A1") (pintype "passive"))
      (node (ref "U503") (pin "C2") (pinfunction "IN-_C2") (pintype "passive"))
    )
    (net (code "18") (name "/THERM.REF") (class "Default")
      (node (ref "TP509") (pin "1") (pinfunction "1_1") (pintype "passive"))
      (node (ref "U501") (pin "A1") (pinfunction "OUT_A1") (pintype "passive"))
      (node (ref "U501") (pin "C2") (pinfunction "IN-_C2") (pintype "passive"))
    )
    (net (code "19") (name "/THERM_IN") (class "Default")
      (node (ref "C513") (pin "2") (pinfunction "2_2") (pintype "passive"))
      (node (ref "J502") (pin "1") (pinfunction "1_1") (pintype "passive"))
      (node (ref "R518") (pin "2") (pinfunction "2_2") (pintype "passive"))
      (node (ref "U503") (pin "C1") (pinfunction "IN+_C1") (pintype "passive"))
    )
    (net (code "20") (name "/THERM_OFST_IN") (class "Default")
      (node (ref "C513") (pin "1") (pinfunction "1_1") (pintype "passive"))
      (node (ref "J503") (pin "1") (pinfunction "1_1") (pintype "passive"))
      (node (ref "R520") (pin "1") (pinfunction "1_1") (pintype "passive"))
      (node (ref "U504") (pin "C1") (pinfunction "IN+_C1") (pintype "passive"))
    )
    (net (code "21") (name "/THERM_REF_IN") (class "Default")
      (node (ref "M508") (pin "3") (pinfunction "D_3") (pintype "passive"))
      (node (ref "R518") (pin "1") (pinfunction "1_1") (pintype "passive"))
      (node (ref "U501") (pin "C1") (pinfunction "IN+_C1") (pintype "passive"))
    )
    (net (code "22") (name "/VCC_CHG") (class "Default")
      (node (ref "C512") (pin "1") (pinfunction "1_1") (pintype "passive"))
      (node (ref "R519") (pin "1") (pinfunction "1_1") (pintype "passive"))
      (node (ref "U502") (pin "5") (pinfunction "VCC_5") (pintype "power_in"))
      (node (ref "U502") (pin "6") (pinfunction "MPPC_6") (pintype "passive"))
    )
    (net (code "23") (name "/VCHG_DISABLE") (class "Default")
      (node (ref "M500") (pin "1") (pinfunction "G_1") (pintype "passive"))
      (node (ref "TP515") (pin "1") (pinfunction "1_1") (pintype "passive"))
    )
    (net (code "24") (name "/VCHG_PGOOD") (class "Default")
      (node (ref "R523") (pin "1") (pinfunction "1_1") (pintype "passive"))
      (node (ref "R524") (pin "2") (pinfunction "2_2") (pintype "passive"))
      (node (ref "TP514") (pin "1") (pinfunction "1_1") (pintype "passive"))
      (node (ref "U502") (pin "13") (pinfunction "PGOOD_13") (pintype "open_collector"))
    )
    (net (code "25") (name "/VDET") (class "Default")
      (node (ref "R509") (pin "2") (pinfunction "2_2") (pintype "passive"))
      (node (ref "R511") (pin "1") (pinfunction "1_1") (pintype "passive"))
      (node (ref "U506") (pin "2") (pinfunction "2_2") (pintype "passive"))
      (node (ref "U508") (pin "5") (pinfunction "5_5") (pintype "passive"))
    )
    (net (code "26") (name "/VOVP") (class "Default")
      (node (ref "R510") (pin "2") (pinfunction "2_2") (pintype "passive"))
      (node (ref "R512") (pin "1") (pinfunction "1_1") (pintype "passive"))
      (node (ref "U507") (pin "2") (pinfunction "2_2") (pintype "passive"))
      (node (ref "U508") (pin "2") (pinfunction "2_2") (pintype "passive"))
    )
    (net (code "27") (name "/VRECT.DETn") (class "Default")
      (node (ref "R513") (pin "2") (pinfunction "2_2") (pintype "passive"))
      (node (ref "TP505") (pin "1") (pinfunction "1_1") (pintype "passive"))
      (node (ref "U508") (pin "3") (pinfunction "3_3") (pintype "passive"))
    )
    (net (code "28") (name "/VRECT.MON") (class "Default")
      (node (ref "TP504") (pin "1") (pinfunction "1_1") (pintype "passive"))
      (node (ref "U500") (pin "A1") (pinfunction "OUT_A1") (pintype "passive"))
      (node (ref "U500") (pin "C2") (pinfunction "IN-_C2") (pintype "passive"))
    )
    (net (code "29") (name "/VRECT.MON_EN") (class "Default")
      (node (ref "C514") (pin "2") (pinfunction "2_2") (pintype "passive"))
      (node (ref "TP503") (pin "1") (pinfunction "1_1") (pintype "passive"))
      (node (ref "U500") (pin "A2") (pinfunction "V+_A2") (pintype "power_in"))
      (node (ref "U505") (pin "2") (pinfunction "2_2") (pintype "passive"))
    )
    (net (code "30") (name "/VRECT.OVPn") (class "Default")
      (node (ref "R514") (pin "2") (pinfunction "2_2") (pintype "passive"))
      (node (ref "TP506") (pin "1") (pinfunction "1_1") (pintype "passive"))
      (node (ref "U507") (pin "6") (pinfunction "6_6") (pintype "passive"))
    )
    (net (code "31") (name "/VRECT_MON_IN") (class "Default")
      (node (ref "R506") (pin "2") (pinfunction "2_2") (pintype "passive"))
      (node (ref "R508") (pin "2") (pinfunction "2_2") (pintype "passive"))
      (node (ref "TP513") (pin "1") (pinfunction "1_1") (pintype "passive"))
      (node (ref "U500") (pin "C1") (pinfunction "IN+_C1") (pintype "passive"))
    )
    (net (code "32") (name "/VS2_CHG") (class "Default")
      (node (ref "R519") (pin "2") (pinfunction "2_2") (pintype "passive"))
      (node (ref "U502") (pin "9") (pinfunction "VS2_9") (pintype "input"))
    )
    (net (code "35") (name "GND") (class "Default")
      (node (ref "C504") (pin "1") (pinfunction "1_1") (pintype "passive"))
      (node (ref "C505") (pin "1") (pinfunction "1_1") (pintype "passive"))
      (node (ref "C508") (pin "2") (pinfunction "2_2") (pintype "passive"))
      (node (ref "C509") (pin "2") (pinfunction "2_2") (pintype "passive"))
      (node (ref "C510") (pin "1") (pinfunction "1_1") (pintype "passive"))
      (node (ref "C511") (pin "1") (pinfunction "1_1") (pintype "passive"))
      (node (ref "C512") (pin "2") (pinfunction "2_2") (pintype "passive"))
      (node (ref "C514") (pin "1") (pinfunction "1_1") (pintype "passive"))
      (node (ref "C515") (pin "1") (pinfunction "1_1") (pintype "passive"))
      (node (ref "C516") (pin "1") (pinfunction "1_1") (pintype "passive"))
      (node (ref "C517") (pin "1") (pinfunction "1_1") (pintype "passive"))
      (node (ref "D502") (pin "2") (pinfunction "K1_2") (pintype "passive"))
      (node (ref "D503") (pin "2") (pinfunction "2_2") (pintype "passive"))
      (node (ref "D504") (pin "2") (pinfunction "2_2") (pintype "passive"))
      (node (ref "J504") (pin "2") (pinfunction "2_2") (pintype "passive"))
      (node (ref "J505") (pin "2") (pinfunction "2_2") (pintype "passive"))
      (node (ref "M500") (pin "2") (pinfunction "S_2") (pintype "passive"))
      (node (ref "R508") (pin "1") (pinfunction "1_1") (pintype "passive"))
      (node (ref "R511") (pin "2") (pinfunction "2_2") (pintype "passive"))
      (node (ref "R512") (pin "2") (pinfunction "2_2") (pintype "passive"))
      (node (ref "R517") (pin "2") (pinfunction "2_2") (pintype "passive"))
      (node (ref "R520") (pin "2") (pinfunction "2_2") (pintype "passive"))
      (node (ref "R523") (pin "2") (pinfunction "2_2") (pintype "passive"))
      (node (ref "U500") (pin "B1") (pinfunction "V-_B1") (pintype "power_in"))
      (node (ref "U501") (pin "B1") (pinfunction "V-_B1") (pintype "power_in"))
      (node (ref "U502") (pin "10") (pinfunction "VS1_10") (pintype "input"))
      (node (ref "U502") (pin "11") (pinfunction "MODE_11") (pintype "input"))
      (node (ref "U502") (pin "12") (pinfunction "EXTVCC_12") (pintype "power_in"))
      (node (ref "U502") (pin "18") (pinfunction "PGND_18") (pintype "power_in"))
      (node (ref "U502") (pin "19") (pinfunction "PGND_19") (pintype "power_in"))
      (node (ref "U502") (pin "21") (pinfunction "EP_21") (pintype "power_in"))
      (node (ref "U502") (pin "7") (pinfunction "GND_7") (pintype "power_in"))
      (node (ref "U502") (pin "8") (pinfunction "GND_8") (pintype "power_in"))
      (node (ref "U503") (pin "B1") (pinfunction "V-_B1") (pintype "power_in"))
      (node (ref "U504") (pin "B1") (pinfunction "V-_B1") (pintype "power_in"))
      (node (ref "U505") (pin "1") (pinfunction "1_1") (pintype "passive"))
      (node (ref "U506") (pin "1") (pinfunction "1_1") (pintype "passive"))
      (node (ref "U507") (pin "1") (pinfunction "1_1") (pintype "passive"))
      (node (ref "U507") (pin "3") (pinfunction "3_3") (pintype "passive"))
      (node (ref "U508") (pin "1") (pinfunction "1_1") (pintype "passive"))
      (node (ref "U508") (pin "4") (pinfunction "4_4") (pintype "passive"))
    )
    (net (code "36") (name "Net-(M500-D)") (class "Default")
      (node (ref "M500") (pin "3") (pinfunction "D_3") (pintype "passive"))
      (node (ref "R522") (pin "2") (pinfunction "2_2") (pintype "passive"))
      (node (ref "U502") (pin "4") (pinfunction "RUN_4") (pintype "input"))
    )
    (net (code "37") (name "Net-(M508-G)") (class "Default")
      (node (ref "M508") (pin "1") (pinfunction "G_1") (pintype "passive"))
      (node (ref "R515") (pin "2") (pinfunction "2_2") (pintype "passive"))
      (node (ref "R517") (pin "1") (pinfunction "1_1") (pintype "passive"))
    )
    (net (code "38") (name "Net-(M508-S)") (class "Default")
      (node (ref "M508") (pin "2") (pinfunction "S_2") (pintype "passive"))
      (node (ref "R516") (pin "1") (pinfunction "1_1") (pintype "passive"))
    )
    (net (code "39") (name "Net-(R500-Pad2)") (class "Default")
      (node (ref "R500") (pin "2") (pinfunction "2_2") (pintype "passive"))
      (node (ref "R504") (pin "1") (pinfunction "1_1") (pintype "passive"))
      (node (ref "U505") (pin "5") (pinfunction "5_5") (pintype "passive"))
    )
    (net (code "40") (name "Net-(R501-Pad2)") (class "Default")
      (node (ref "R501") (pin "2") (pinfunction "2_2") (pintype "passive"))
      (node (ref "R507") (pin "1") (pinfunction "1_1") (pintype "passive"))
      (node (ref "U507") (pin "5") (pinfunction "5_5") (pintype "passive"))
    )
    (net (code "41") (name "Net-(R502-Pad2)") (class "Default")
      (node (ref "R502") (pin "2") (pinfunction "2_2") (pintype "passive"))
      (node (ref "U507") (pin "4") (pinfunction "4_4") (pintype "passive"))
    )
    (net (code "42") (name "Net-(R504-Pad2)") (class "Default")
      (node (ref "R504") (pin "2") (pinfunction "2_2") (pintype "passive"))
      (node (ref "U505") (pin "6") (pinfunction "6_6") (pintype "passive"))
    )
    (net (code "43") (name "Net-(R505-Pad2)") (class "Default")
      (node (ref "R505") (pin "2") (pinfunction "2_2") (pintype "passive"))
      (node (ref "U506") (pin "6") (pinfunction "6_6") (pintype "passive"))
    )
    (net (code "44") (name "Net-(R506-Pad1)") (class "Default")
      (node (ref "R506") (pin "1") (pinfunction "1_1") (pintype "passive"))
      (node (ref "U505") (pin "3") (pinfunction "3_3") (pintype "passive"))
    )
    (net (code "45") (name "Net-(R507-Pad2)") (class "Default")
      (node (ref "R507") (pin "2") (pinfunction "2_2") (pintype "passive"))
      (node (ref "U508") (pin "6") (pinfunction "6_6") (pintype "passive"))
    )
    (net (code "46") (name "unconnected-(U500-NC-PadB2)") (class "Default")
      (node (ref "U500") (pin "B2") (pinfunction "NC_B2") (pintype "power_in+no_connect"))
    )
    (net (code "47") (name "unconnected-(U501-NC-PadB2)") (class "Default")
      (node (ref "U501") (pin "B2") (pinfunction "NC_B2") (pintype "power_in+no_connect"))
    )
    (net (code "48") (name "unconnected-(U502-NC-Pad17)") (class "Default")
      (node (ref "U502") (pin "17") (pinfunction "NC_17") (pintype "passive+no_connect"))
    )
    (net (code "49") (name "unconnected-(U503-NC-PadB2)") (class "Default")
      (node (ref "U503") (pin "B2") (pinfunction "NC_B2") (pintype "power_in+no_connect"))
    )
    (net (code "50") (name "unconnected-(U504-NC-PadB2)") (class "Default")
      (node (ref "U504") (pin "B2") (pinfunction "NC_B2") (pintype "power_in+no_connect"))
    )
    (net (code "51") (name "unconnected-(U506-Pad3)") (class "Default")
      (node (ref "U506") (pin "3") (pinfunction "3_3") (pintype "passive+no_connect"))
    )
    (net (code "52") (name "unconnected-(U506-Pad4)") (class "Default")
      (node (ref "U506") (pin "4") (pinfunction "4_4") (pintype "passive+no_connect"))
    )
    (net (code "53") (name "unconnected-(U506-Pad5)") (class "Default")
      (node (ref "U506") (pin "5") (pinfunction "5_5") (pintype "passive+no_connect"))
    )
  )
)
